# MotorDriver.net
KiCad netlist of a schematic drawn in EAGLE
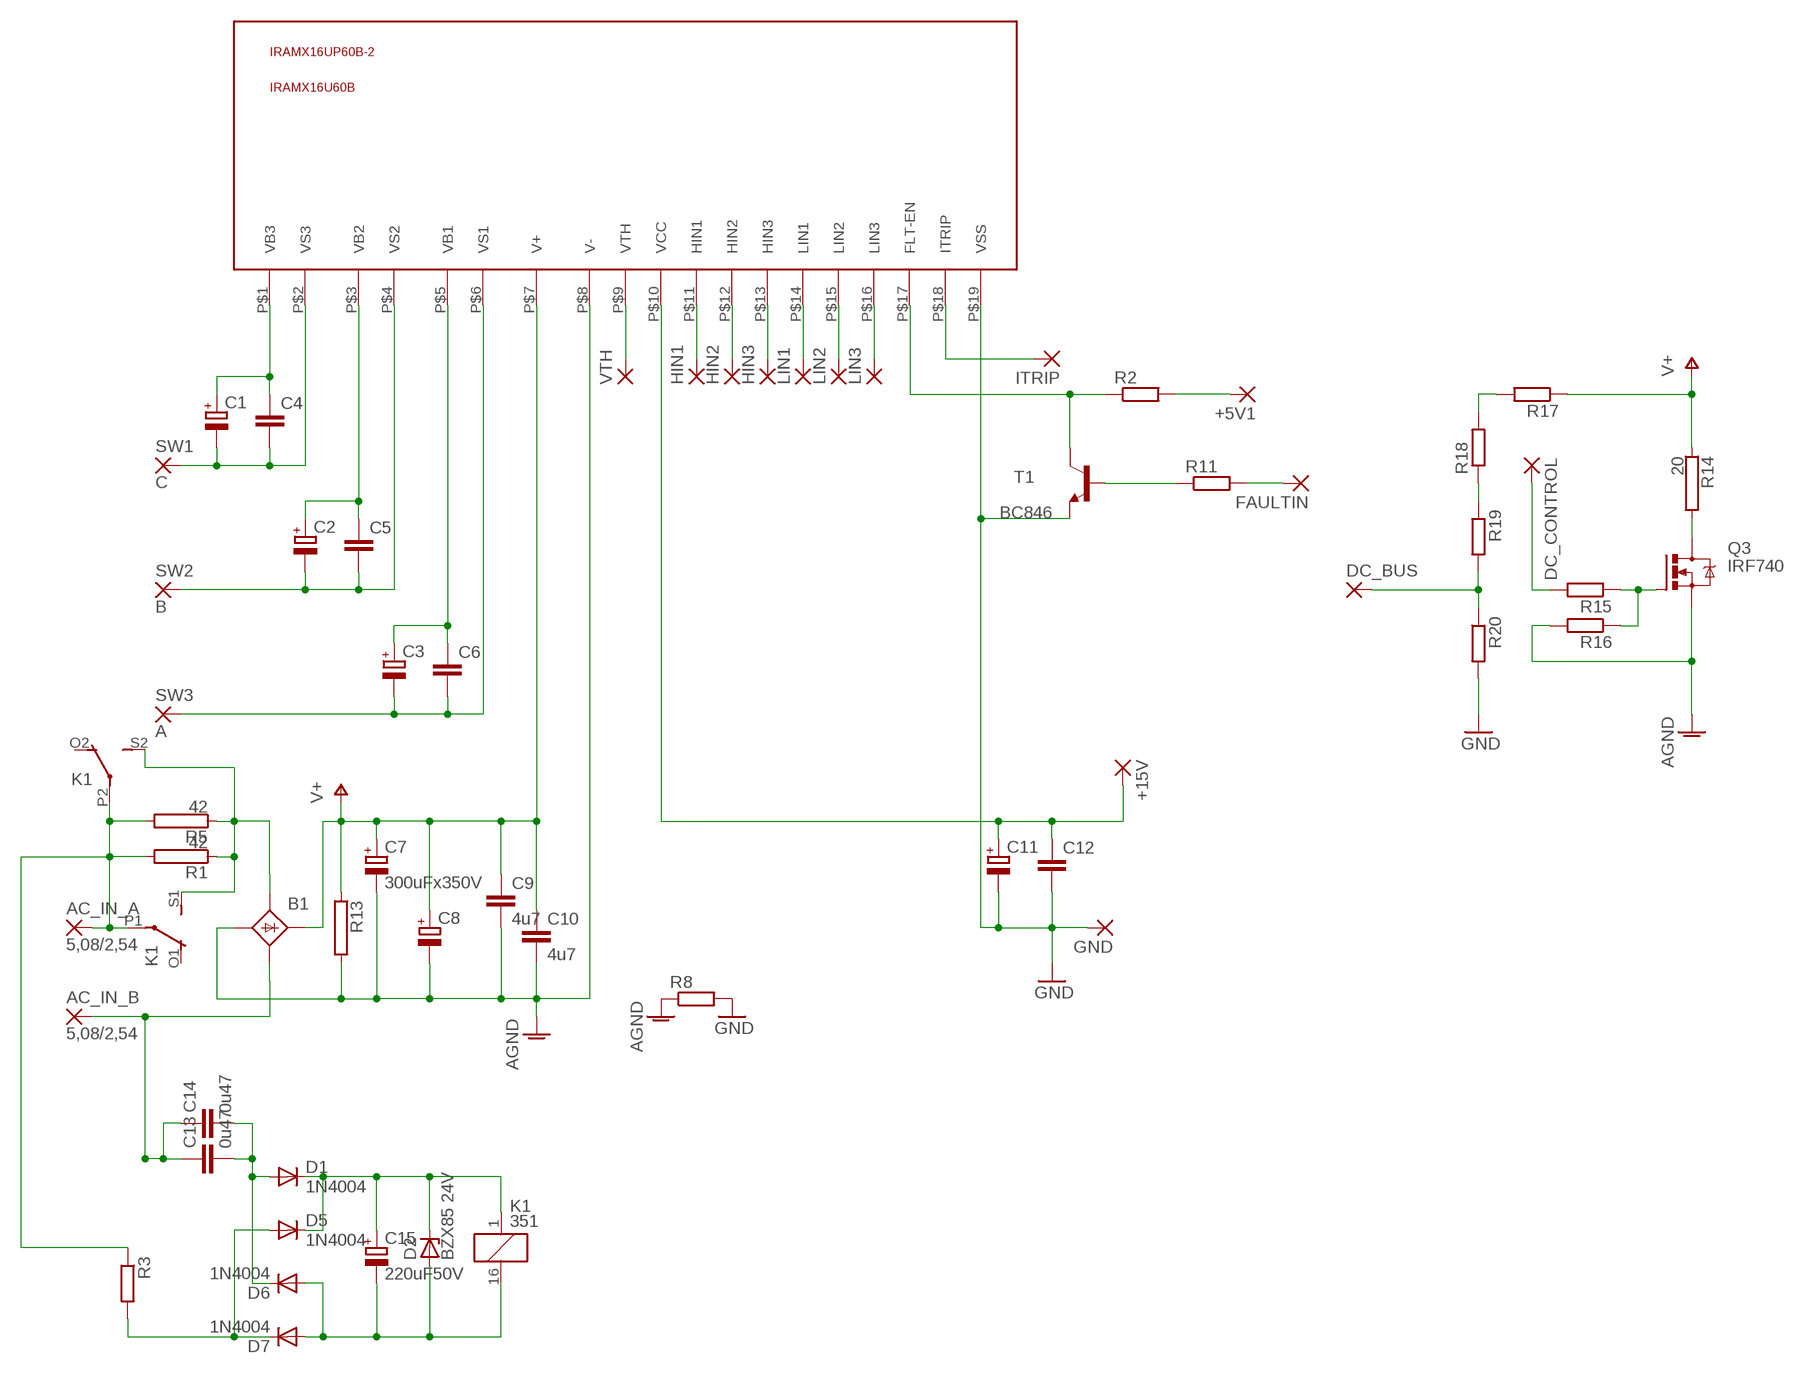
[diagram p0: schematic, sheet 1]

(export (version "E")
  (design (tool "Eeschema 10.0.6"))
  (components
    (comp (ref "+5V1")
      (value "3,81/1,3")
      (footprint "eagle-import:3,81_1,3")
      (libsource (lib "eagle-import") (part "3,81/1,3"))
    )
    (comp (ref "+15V")
      (value "3,81/1,3")
      (footprint "eagle-import:3,81_1,3")
      (libsource (lib "eagle-import") (part "3,81/1,3"))
    )
    (comp (ref "AC_IN_A")
      (value "5,08/2,54")
      (footprint "eagle-import:5,08_2,54")
      (libsource (lib "eagle-import") (part "5,08/2,54"))
    )
    (comp (ref "AC_IN_B")
      (value "5,08/2,54")
      (footprint "eagle-import:5,08_2,54")
      (libsource (lib "eagle-import") (part "5,08/2,54"))
    )
    (comp (ref "B1")
      (value "B25A-")
      (footprint "eagle-import:B25A-")
      (libsource (lib "eagle-import") (part "B25A-"))
    )
    (comp (ref "C1")
      (value "CPOL-EUE2,5-6E")
      (footprint "eagle-import:E2,5-6E")
      (libsource (lib "eagle-import") (part "CPOL-EUE2,5-6E"))
    )
    (comp (ref "C2")
      (value "CPOL-EUE2,5-6E")
      (footprint "eagle-import:E2,5-6E")
      (libsource (lib "eagle-import") (part "CPOL-EUE2,5-6E"))
    )
    (comp (ref "C3")
      (value "CPOL-EUE2,5-6E")
      (footprint "eagle-import:E2,5-6E")
      (libsource (lib "eagle-import") (part "CPOL-EUE2,5-6E"))
    )
    (comp (ref "C4")
      (value "C-EUC1206")
      (footprint "eagle-import:C1206")
      (libsource (lib "eagle-import") (part "C-EUC1206"))
    )
    (comp (ref "C5")
      (value "C-EUC1206")
      (footprint "eagle-import:C1206")
      (libsource (lib "eagle-import") (part "C-EUC1206"))
    )
    (comp (ref "C6")
      (value "C-EUC1206")
      (footprint "eagle-import:C1206")
      (libsource (lib "eagle-import") (part "C-EUC1206"))
    )
    (comp (ref "C7")
      (value "300uFx350V")
      (footprint "eagle-import:EB35D")
      (libsource (lib "eagle-import") (part "CPOL-EUE10-35"))
    )
    (comp (ref "C8")
      (value "CPOL-EUE10-35")
      (footprint "eagle-import:EB35D")
      (libsource (lib "eagle-import") (part "CPOL-EUE10-35"))
    )
    (comp (ref "C9")
      (value "4u7")
      (footprint "eagle-import:C225-074X268")
      (libsource (lib "eagle-import") (part "C-EU225-074X268"))
    )
    (comp (ref "C10")
      (value "4u7")
      (footprint "eagle-import:C225-074X268")
      (libsource (lib "eagle-import") (part "C-EU225-074X268"))
    )
    (comp (ref "C11")
      (value "CPOL-EUE2,5-6E")
      (footprint "eagle-import:E2,5-6E")
      (libsource (lib "eagle-import") (part "CPOL-EUE2,5-6E"))
    )
    (comp (ref "C12")
      (value "C-EUC1206")
      (footprint "eagle-import:C1206")
      (libsource (lib "eagle-import") (part "C-EUC1206"))
    )
    (comp (ref "C13")
      (value "0u47")
      (footprint "eagle-import:C102-064X133")
      (libsource (lib "eagle-import") (part "C-EU102-064X133"))
    )
    (comp (ref "C14")
      (value "0u47")
      (footprint "eagle-import:C102-064X133")
      (libsource (lib "eagle-import") (part "C-EU102-064X133"))
    )
    (comp (ref "C15")
      (value "220uF50V")
      (footprint "eagle-import:E3,5-10")
      (libsource (lib "eagle-import") (part "CPOL-EUE3.5-10"))
    )
    (comp (ref "D1")
      (value "1N4004")
      (footprint "eagle-import:DO41-10")
      (libsource (lib "eagle-import") (part "1N4004"))
    )
    (comp (ref "D2")
      (value "BZX85 24V")
      (footprint "eagle-import:DO41Z10")
      (libsource (lib "eagle-import") (part "BZX85"))
    )
    (comp (ref "D5")
      (value "1N4004")
      (footprint "eagle-import:DO41-10")
      (libsource (lib "eagle-import") (part "1N4004"))
    )
    (comp (ref "D6")
      (value "1N4004")
      (footprint "eagle-import:DO41-10")
      (libsource (lib "eagle-import") (part "1N4004"))
    )
    (comp (ref "D7")
      (value "1N4004")
      (footprint "eagle-import:DO41-10")
      (libsource (lib "eagle-import") (part "1N4004"))
    )
    (comp (ref "DC_BUS")
      (value "3,81/1,3")
      (footprint "eagle-import:3,81_1,3")
      (libsource (lib "eagle-import") (part "3,81/1,3"))
    )
    (comp (ref "DC_CONTROL")
      (value "3,81/1,3")
      (footprint "eagle-import:3,81_1,3")
      (libsource (lib "eagle-import") (part "3,81/1,3"))
    )
    (comp (ref "FAULTIN")
      (value "3,81/1,3")
      (footprint "eagle-import:3,81_1,3")
      (libsource (lib "eagle-import") (part "3,81/1,3"))
    )
    (comp (ref "GND")
      (value "3,81/1,3")
      (footprint "eagle-import:3,81_1,3")
      (libsource (lib "eagle-import") (part "3,81/1,3"))
    )
    (comp (ref "HIN1")
      (value "2,54/0,8")
      (footprint "eagle-import:2,54_0,8")
      (libsource (lib "eagle-import") (part "2,54/0,8"))
    )
    (comp (ref "HIN2")
      (value "2,54/0,8")
      (footprint "eagle-import:2,54_0,8")
      (libsource (lib "eagle-import") (part "2,54/0,8"))
    )
    (comp (ref "HIN3")
      (value "2,54/0,8")
      (footprint "eagle-import:2,54_0,8")
      (libsource (lib "eagle-import") (part "2,54/0,8"))
    )
    (comp (ref "IC1")
      (value "IRAMX16UP60B-2")
      (footprint "eagle-import:SIP2")
      (libsource (lib "eagle-import") (part "IRAMX16UP60B-2"))
    )
    (comp (ref "ITRIP")
      (value "2,54/0,8")
      (footprint "eagle-import:2,54_0,8")
      (libsource (lib "eagle-import") (part "2,54/0,8"))
    )
    (comp (ref "K1")
      (value "351")
      (footprint "eagle-import:351")
      (libsource (lib "eagle-import") (part "351"))
    )
    (comp (ref "LIN1")
      (value "2,54/0,8")
      (footprint "eagle-import:2,54_0,8")
      (libsource (lib "eagle-import") (part "2,54/0,8"))
    )
    (comp (ref "LIN2")
      (value "2,54/0,8")
      (footprint "eagle-import:2,54_0,8")
      (libsource (lib "eagle-import") (part "2,54/0,8"))
    )
    (comp (ref "LIN3")
      (value "2,54/0,8")
      (footprint "eagle-import:2,54_0,8")
      (libsource (lib "eagle-import") (part "2,54/0,8"))
    )
    (comp (ref "Q3")
      (value "IRF740")
      (footprint "eagle-import:TO220BV")
      (libsource (lib "eagle-import") (part "IRF740"))
    )
    (comp (ref "R1")
      (value "42")
      (footprint "eagle-import:AC05")
      (libsource (lib "eagle-import") (part "RAC05"))
    )
    (comp (ref "R2")
      (value "R-EU_0204/7")
      (footprint "eagle-import:0204_7")
      (libsource (lib "eagle-import") (part "R-EU_0204/7"))
    )
    (comp (ref "R3")
      (value "R-EU_0204/7")
      (footprint "eagle-import:0204_7")
      (libsource (lib "eagle-import") (part "R-EU_0204/7"))
    )
    (comp (ref "R5")
      (value "42")
      (footprint "eagle-import:AC05")
      (libsource (lib "eagle-import") (part "RAC05"))
    )
    (comp (ref "R8")
      (value "R-EU_0204/7")
      (footprint "eagle-import:0204_7")
      (libsource (lib "eagle-import") (part "R-EU_0204/7"))
    )
    (comp (ref "R11")
      (value "R-EU_0204/7")
      (footprint "eagle-import:0204_7")
      (libsource (lib "eagle-import") (part "R-EU_0204/7"))
    )
    (comp (ref "R13")
      (value "RAC04")
      (footprint "eagle-import:AC04")
      (libsource (lib "eagle-import") (part "RAC04"))
    )
    (comp (ref "R14")
      (value "20")
      (footprint "eagle-import:AC05")
      (libsource (lib "eagle-import") (part "RAC05"))
    )
    (comp (ref "R15")
      (value "R-EU_0204/7")
      (footprint "eagle-import:0204_7")
      (libsource (lib "eagle-import") (part "R-EU_0204/7"))
    )
    (comp (ref "R16")
      (value "R-EU_0204/7")
      (footprint "eagle-import:0204_7")
      (libsource (lib "eagle-import") (part "R-EU_0204/7"))
    )
    (comp (ref "R17")
      (value "R-EU_0204/7")
      (footprint "eagle-import:0204_7")
      (libsource (lib "eagle-import") (part "R-EU_0204/7"))
    )
    (comp (ref "R18")
      (value "R-EU_0204/7")
      (footprint "eagle-import:0204_7")
      (libsource (lib "eagle-import") (part "R-EU_0204/7"))
    )
    (comp (ref "R19")
      (value "R-EU_0204/7")
      (footprint "eagle-import:0204_7")
      (libsource (lib "eagle-import") (part "R-EU_0204/7"))
    )
    (comp (ref "R20")
      (value "R-EU_0204/7")
      (footprint "eagle-import:0204_7")
      (libsource (lib "eagle-import") (part "R-EU_0204/7"))
    )
    (comp (ref "SW1")
      (value "C")
      (footprint "eagle-import:5,08_2,54")
      (libsource (lib "eagle-import") (part "5,08/2,54"))
    )
    (comp (ref "SW2")
      (value "B")
      (footprint "eagle-import:5,08_2,54")
      (libsource (lib "eagle-import") (part "5,08/2,54"))
    )
    (comp (ref "SW3")
      (value "A")
      (footprint "eagle-import:5,08_2,54")
      (libsource (lib "eagle-import") (part "5,08/2,54"))
    )
    (comp (ref "T1")
      (value "BC846")
      (footprint "eagle-import:SOT23")
      (libsource (lib "eagle-import") (part "BC846"))
    )
    (comp (ref "VTH")
      (value "2,54/0,8")
      (footprint "eagle-import:2,54_0,8")
      (libsource (lib "eagle-import") (part "2,54/0,8"))
    )
  )
  (nets
    (net (code "1") (name "AGND") (class "Default")
      (node (ref "B1") (pin "-") (pinfunction "-_-") (pintype "passive"))
      (node (ref "B1") (pin "-1") (pinfunction "-_-1") (pintype "passive"))
      (node (ref "C10") (pin "2") (pinfunction "2_2") (pintype "passive"))
      (node (ref "C7") (pin "-") (pinfunction "-_-") (pintype "passive"))
      (node (ref "C8") (pin "-") (pinfunction "-_-") (pintype "passive"))
      (node (ref "C9") (pin "2") (pinfunction "2_2") (pintype "passive"))
      (node (ref "IC1") (pin "P$8") (pinfunction "V-_P$8") (pintype "bidirectional"))
      (node (ref "Q3") (pin "S") (pinfunction "S_S") (pintype "passive"))
      (node (ref "R13") (pin "2") (pinfunction "2_2") (pintype "passive"))
      (node (ref "R16") (pin "2") (pinfunction "2_2") (pintype "passive"))
      (node (ref "R8") (pin "1") (pinfunction "1_1") (pintype "passive"))
    )
    (net (code "2") (name "GND") (class "Default")
      (node (ref "C11") (pin "-") (pinfunction "-_-") (pintype "passive"))
      (node (ref "C12") (pin "2") (pinfunction "2_2") (pintype "passive"))
      (node (ref "GND") (pin "1") (pinfunction "P_1") (pintype "passive"))
      (node (ref "IC1") (pin "P$19") (pinfunction "VSS_P$19") (pintype "bidirectional"))
      (node (ref "R20") (pin "2") (pinfunction "2_2") (pintype "passive"))
      (node (ref "R8") (pin "2") (pinfunction "2_2") (pintype "passive"))
      (node (ref "T1") (pin "2") (pinfunction "E_2") (pintype "passive"))
    )
    (net (code "3") (name "Net-(+5V1-P)") (class "Default")
      (node (ref "+5V1") (pin "1") (pinfunction "P_1") (pintype "passive"))
      (node (ref "R2") (pin "2") (pinfunction "2_2") (pintype "passive"))
    )
    (net (code "4") (name "Net-(+15V-P)") (class "Default")
      (node (ref "+15V") (pin "1") (pinfunction "P_1") (pintype "passive"))
      (node (ref "C11") (pin "+") (pinfunction "+_+") (pintype "passive"))
      (node (ref "C12") (pin "1") (pinfunction "1_1") (pintype "passive"))
      (node (ref "IC1") (pin "P$10") (pinfunction "VCC_P$10") (pintype "bidirectional"))
    )
    (net (code "5") (name "Net-(AC_IN_A-P)") (class "Default")
      (node (ref "AC_IN_A") (pin "P$1") (pinfunction "P_P$1") (pintype "passive"))
      (node (ref "K1") (pin "P1") (pinfunction "P_P1") (pintype "passive"))
      (node (ref "K1") (pin "P2") (pinfunction "P_P2") (pintype "passive"))
      (node (ref "R1") (pin "2") (pinfunction "2_2") (pintype "passive"))
      (node (ref "R3") (pin "1") (pinfunction "1_1") (pintype "passive"))
      (node (ref "R5") (pin "2") (pinfunction "2_2") (pintype "passive"))
    )
    (net (code "6") (name "Net-(AC_IN_B-P)") (class "Default")
      (node (ref "AC_IN_B") (pin "P$1") (pinfunction "P_P$1") (pintype "passive"))
      (node (ref "B1") (pin "AC2") (pinfunction "AC2_AC2") (pintype "passive"))
      (node (ref "B1") (pin "AC2-") (pinfunction "AC2_AC2-") (pintype "passive"))
      (node (ref "C13") (pin "1") (pinfunction "1_1") (pintype "passive"))
      (node (ref "C14") (pin "1") (pinfunction "1_1") (pintype "passive"))
    )
    (net (code "7") (name "Net-(C13-Pad2)") (class "Default")
      (node (ref "C13") (pin "2") (pinfunction "2_2") (pintype "passive"))
      (node (ref "C14") (pin "2") (pinfunction "2_2") (pintype "passive"))
      (node (ref "D1") (pin "A") (pinfunction "A_A") (pintype "passive"))
      (node (ref "D6") (pin "C") (pinfunction "C_C") (pintype "passive"))
    )
    (net (code "8") (name "Net-(C15-Pad+)") (class "Default")
      (node (ref "C15") (pin "+") (pinfunction "+_+") (pintype "passive"))
      (node (ref "D1") (pin "C") (pinfunction "C_C") (pintype "passive"))
      (node (ref "D2") (pin "C") (pinfunction "C_C") (pintype "passive"))
      (node (ref "D5") (pin "C") (pinfunction "C_C") (pintype "passive"))
      (node (ref "K1") (pin "1") (pinfunction "1_1") (pintype "passive"))
    )
    (net (code "9") (name "Net-(D5-PadA)") (class "Default")
      (node (ref "D5") (pin "A") (pinfunction "A_A") (pintype "passive"))
      (node (ref "D7") (pin "C") (pinfunction "C_C") (pintype "passive"))
      (node (ref "R3") (pin "2") (pinfunction "2_2") (pintype "passive"))
    )
    (net (code "10") (name "Net-(DC_BUS-P)") (class "Default")
      (node (ref "DC_BUS") (pin "1") (pinfunction "P_1") (pintype "passive"))
      (node (ref "R19") (pin "2") (pinfunction "2_2") (pintype "passive"))
      (node (ref "R20") (pin "1") (pinfunction "1_1") (pintype "passive"))
    )
    (net (code "11") (name "Net-(DC_CONTROL-P)") (class "Default")
      (node (ref "DC_CONTROL") (pin "1") (pinfunction "P_1") (pintype "passive"))
      (node (ref "R15") (pin "2") (pinfunction "2_2") (pintype "passive"))
    )
    (net (code "12") (name "Net-(FAULTIN-P)") (class "Default")
      (node (ref "FAULTIN") (pin "1") (pinfunction "P_1") (pintype "passive"))
      (node (ref "R11") (pin "2") (pinfunction "2_2") (pintype "passive"))
    )
    (net (code "13") (name "Net-(HIN1-P)") (class "Default")
      (node (ref "HIN1") (pin "1") (pinfunction "P_1") (pintype "passive"))
      (node (ref "IC1") (pin "P$11") (pinfunction "HIN1_P$11") (pintype "bidirectional"))
    )
    (net (code "14") (name "Net-(HIN2-P)") (class "Default")
      (node (ref "HIN2") (pin "1") (pinfunction "P_1") (pintype "passive"))
      (node (ref "IC1") (pin "P$12") (pinfunction "HIN2_P$12") (pintype "bidirectional"))
    )
    (net (code "15") (name "Net-(HIN3-P)") (class "Default")
      (node (ref "HIN3") (pin "1") (pinfunction "P_1") (pintype "passive"))
      (node (ref "IC1") (pin "P$13") (pinfunction "HIN3_P$13") (pintype "bidirectional"))
    )
    (net (code "16") (name "Net-(IC1-FLT-EN)") (class "Default")
      (node (ref "IC1") (pin "P$17") (pinfunction "FLT-EN_P$17") (pintype "bidirectional"))
      (node (ref "R2") (pin "1") (pinfunction "1_1") (pintype "passive"))
      (node (ref "T1") (pin "3") (pinfunction "C_3") (pintype "passive"))
    )
    (net (code "17") (name "Net-(IC1-ITRIP)") (class "Default")
      (node (ref "IC1") (pin "P$18") (pinfunction "ITRIP_P$18") (pintype "bidirectional"))
      (node (ref "ITRIP") (pin "1") (pinfunction "P_1") (pintype "passive"))
    )
    (net (code "18") (name "Net-(IC1-LIN1)") (class "Default")
      (node (ref "IC1") (pin "P$14") (pinfunction "LIN1_P$14") (pintype "bidirectional"))
      (node (ref "LIN1") (pin "1") (pinfunction "P_1") (pintype "passive"))
    )
    (net (code "19") (name "Net-(IC1-LIN2)") (class "Default")
      (node (ref "IC1") (pin "P$15") (pinfunction "LIN2_P$15") (pintype "bidirectional"))
      (node (ref "LIN2") (pin "1") (pinfunction "P_1") (pintype "passive"))
    )
    (net (code "20") (name "Net-(IC1-LIN3)") (class "Default")
      (node (ref "IC1") (pin "P$16") (pinfunction "LIN3_P$16") (pintype "bidirectional"))
      (node (ref "LIN3") (pin "1") (pinfunction "P_1") (pintype "passive"))
    )
    (net (code "21") (name "Net-(IC1-VB1)") (class "Default")
      (node (ref "C3") (pin "+") (pinfunction "+_+") (pintype "passive"))
      (node (ref "C6") (pin "1") (pinfunction "1_1") (pintype "passive"))
      (node (ref "IC1") (pin "P$5") (pinfunction "VB1_P$5") (pintype "bidirectional"))
    )
    (net (code "22") (name "Net-(IC1-VB2)") (class "Default")
      (node (ref "C2") (pin "+") (pinfunction "+_+") (pintype "passive"))
      (node (ref "C5") (pin "1") (pinfunction "1_1") (pintype "passive"))
      (node (ref "IC1") (pin "P$3") (pinfunction "VB2_P$3") (pintype "bidirectional"))
    )
    (net (code "23") (name "Net-(IC1-VB3)") (class "Default")
      (node (ref "C1") (pin "+") (pinfunction "+_+") (pintype "passive"))
      (node (ref "C4") (pin "1") (pinfunction "1_1") (pintype "passive"))
      (node (ref "IC1") (pin "P$1") (pinfunction "VB3_P$1") (pintype "bidirectional"))
    )
    (net (code "24") (name "Net-(IC1-VS1)") (class "Default")
      (node (ref "C3") (pin "-") (pinfunction "-_-") (pintype "passive"))
      (node (ref "C6") (pin "2") (pinfunction "2_2") (pintype "passive"))
      (node (ref "IC1") (pin "P$6") (pinfunction "VS1_P$6") (pintype "bidirectional"))
      (node (ref "SW3") (pin "P$1") (pinfunction "P_P$1") (pintype "passive"))
    )
    (net (code "25") (name "Net-(IC1-VS2)") (class "Default")
      (node (ref "C2") (pin "-") (pinfunction "-_-") (pintype "passive"))
      (node (ref "C5") (pin "2") (pinfunction "2_2") (pintype "passive"))
      (node (ref "IC1") (pin "P$4") (pinfunction "VS2_P$4") (pintype "bidirectional"))
      (node (ref "SW2") (pin "P$1") (pinfunction "P_P$1") (pintype "passive"))
    )
    (net (code "26") (name "Net-(IC1-VS3)") (class "Default")
      (node (ref "C1") (pin "-") (pinfunction "-_-") (pintype "passive"))
      (node (ref "C4") (pin "2") (pinfunction "2_2") (pintype "passive"))
      (node (ref "IC1") (pin "P$2") (pinfunction "VS3_P$2") (pintype "bidirectional"))
      (node (ref "SW1") (pin "P$1") (pinfunction "P_P$1") (pintype "passive"))
    )
    (net (code "27") (name "Net-(IC1-VTH)") (class "Default")
      (node (ref "IC1") (pin "P$9") (pinfunction "VTH_P$9") (pintype "bidirectional"))
      (node (ref "VTH") (pin "1") (pinfunction "P_1") (pintype "passive"))
    )
    (net (code "28") (name "Net-(K1A-2)") (class "Default")
      (node (ref "C15") (pin "-") (pinfunction "-_-") (pintype "passive"))
      (node (ref "D2") (pin "A") (pinfunction "A_A") (pintype "passive"))
      (node (ref "D6") (pin "A") (pinfunction "A_A") (pintype "passive"))
      (node (ref "D7") (pin "A") (pinfunction "A_A") (pintype "passive"))
      (node (ref "K1") (pin "16") (pinfunction "2_16") (pintype "passive"))
    )
    (net (code "29") (name "Net-(K1B-S)") (class "Default")
      (node (ref "B1") (pin "AC1") (pinfunction "AC1_AC1") (pintype "passive"))
      (node (ref "B1") (pin "AC1-") (pinfunction "AC1_AC1-") (pintype "passive"))
      (node (ref "K1") (pin "S1") (pinfunction "S_S1") (pintype "passive"))
      (node (ref "K1") (pin "S2") (pinfunction "S_S2") (pintype "passive"))
      (node (ref "R1") (pin "1") (pinfunction "1_1") (pintype "passive"))
      (node (ref "R5") (pin "1") (pinfunction "1_1") (pintype "passive"))
    )
    (net (code "30") (name "Net-(Q3-PadD)") (class "Default")
      (node (ref "Q3") (pin "D") (pinfunction "D_D") (pintype "passive"))
      (node (ref "R14") (pin "2") (pinfunction "2_2") (pintype "passive"))
    )
    (net (code "31") (name "Net-(Q3-PadG)") (class "Default")
      (node (ref "Q3") (pin "G") (pinfunction "G_G") (pintype "passive"))
      (node (ref "R15") (pin "1") (pinfunction "1_1") (pintype "passive"))
      (node (ref "R16") (pin "1") (pinfunction "1_1") (pintype "passive"))
    )
    (net (code "32") (name "Net-(R17-Pad2)") (class "Default")
      (node (ref "R17") (pin "2") (pinfunction "2_2") (pintype "passive"))
      (node (ref "R18") (pin "2") (pinfunction "2_2") (pintype "passive"))
    )
    (net (code "33") (name "Net-(R18-Pad1)") (class "Default")
      (node (ref "R18") (pin "1") (pinfunction "1_1") (pintype "passive"))
      (node (ref "R19") (pin "1") (pinfunction "1_1") (pintype "passive"))
    )
    (net (code "34") (name "Net-(T1-B)") (class "Default")
      (node (ref "R11") (pin "1") (pinfunction "1_1") (pintype "passive"))
      (node (ref "T1") (pin "1") (pinfunction "B_1") (pintype "passive"))
    )
    (net (code "35") (name "V+") (class "Default")
      (node (ref "B1") (pin "+") (pinfunction "+_+") (pintype "passive"))
      (node (ref "B1") (pin "+1") (pinfunction "+_+1") (pintype "passive"))
      (node (ref "C10") (pin "1") (pinfunction "1_1") (pintype "passive"))
      (node (ref "C7") (pin "+") (pinfunction "+_+") (pintype "passive"))
      (node (ref "C8") (pin "+") (pinfunction "+_+") (pintype "passive"))
      (node (ref "C9") (pin "1") (pinfunction "1_1") (pintype "passive"))
      (node (ref "IC1") (pin "P$7") (pinfunction "V+_P$7") (pintype "bidirectional"))
      (node (ref "R13") (pin "1") (pinfunction "1_1") (pintype "passive"))
      (node (ref "R14") (pin "1") (pinfunction "1_1") (pintype "passive"))
      (node (ref "R17") (pin "1") (pinfunction "1_1") (pintype "passive"))
    )
    (net (code "36") (name "unconnected-(K1B-O-PadO1)") (class "Default")
      (node (ref "K1") (pin "O1") (pinfunction "O_O1") (pintype "passive"))
    )
    (net (code "37") (name "unconnected-(K1C-O-PadO2)") (class "Default")
      (node (ref "K1") (pin "O2") (pinfunction "O_O2") (pintype "passive"))
    )
  )
)
